# Borden-Arus.net
KiCad netlist of a schematic drawn in EAGLE
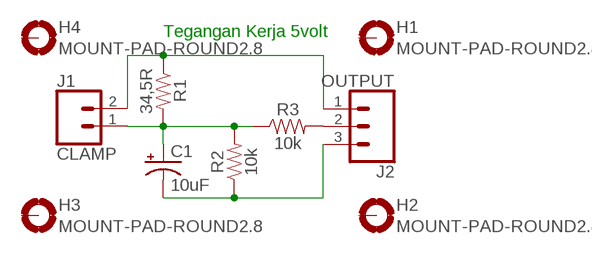
[diagram p0: schematic, sheet 1]

(export (version "E")
  (design (tool "Eeschema 10.0.6"))
  (components
    (comp (ref "C1")
      (value "10uF")
      (footprint "eagle-import:CPOL-RADIAL-2.5MM-5MM")
      (libsource (lib "eagle-import") (part "10UF-POLAR-RADIAL-2.5MM-25V-20%"))
    )
    (comp (ref "H1")
      (value "MOUNT-PAD-ROUND2.8")
      (footprint "eagle-import:2,8-PAD")
      (libsource (lib "eagle-import") (part "MOUNT-PAD-ROUND2.8"))
    )
    (comp (ref "H2")
      (value "MOUNT-PAD-ROUND2.8")
      (footprint "eagle-import:2,8-PAD")
      (libsource (lib "eagle-import") (part "MOUNT-PAD-ROUND2.8"))
    )
    (comp (ref "H3")
      (value "MOUNT-PAD-ROUND2.8")
      (footprint "eagle-import:2,8-PAD")
      (libsource (lib "eagle-import") (part "MOUNT-PAD-ROUND2.8"))
    )
    (comp (ref "H4")
      (value "MOUNT-PAD-ROUND2.8")
      (footprint "eagle-import:2,8-PAD")
      (libsource (lib "eagle-import") (part "MOUNT-PAD-ROUND2.8"))
    )
    (comp (ref "J1")
      (value "CLAMP")
      (footprint "eagle-import:1X02")
      (libsource (lib "eagle-import") (part "CONN_02"))
    )
    (comp (ref "J2")
      (value "OUTPUT")
      (footprint "eagle-import:1X03")
      (libsource (lib "eagle-import") (part "CONN_03"))
    )
    (comp (ref "R1")
      (value "34,5R")
      (footprint "eagle-import:AXIAL-0.3")
      (libsource (lib "eagle-import") (part "1KOHM-HORIZ-1/4W-1%"))
    )
    (comp (ref "R2")
      (value "10k")
      (footprint "eagle-import:AXIAL-0.3")
      (libsource (lib "eagle-import") (part "1KOHM-HORIZ-1/4W-1%"))
    )
    (comp (ref "R3")
      (value "10k")
      (footprint "eagle-import:AXIAL-0.3")
      (libsource (lib "eagle-import") (part "1KOHM-HORIZ-1/4W-1%"))
    )
  )
  (nets
    (net (code "1") (name "Net-(C1-+)") (class "Default")
      (node (ref "C1") (pin "1") (pinfunction "+_1") (pintype "passive"))
      (node (ref "J1") (pin "1") (pinfunction "1_1") (pintype "passive"))
      (node (ref "R1") (pin "P$2") (pinfunction "2_P$2") (pintype "passive"))
      (node (ref "R2") (pin "P$2") (pinfunction "2_P$2") (pintype "passive"))
      (node (ref "R3") (pin "P$1") (pinfunction "1_P$1") (pintype "passive"))
    )
    (net (code "2") (name "Net-(C1--)") (class "Default")
      (node (ref "C1") (pin "2") (pinfunction "-_2") (pintype "passive"))
      (node (ref "J2") (pin "3") (pinfunction "3_3") (pintype "passive"))
      (node (ref "R2") (pin "P$1") (pinfunction "1_P$1") (pintype "passive"))
    )
    (net (code "3") (name "Net-(R1-1)") (class "Default")
      (node (ref "J1") (pin "2") (pinfunction "2_2") (pintype "passive"))
      (node (ref "J2") (pin "1") (pinfunction "1_1") (pintype "passive"))
      (node (ref "R1") (pin "P$1") (pinfunction "1_P$1") (pintype "passive"))
    )
    (net (code "4") (name "Net-(R3-2)") (class "Default")
      (node (ref "J2") (pin "2") (pinfunction "2_2") (pintype "passive"))
      (node (ref "R3") (pin "P$2") (pinfunction "2_P$2") (pintype "passive"))
    )
    (net (code "5") (name "unconnected-(H1-MOUNT-PadB2,8)") (class "Default")
      (node (ref "H1") (pin "B2,8") (pinfunction "MOUNT_B2,8") (pintype "passive"))
    )
    (net (code "6") (name "unconnected-(H2-MOUNT-PadB2,8)") (class "Default")
      (node (ref "H2") (pin "B2,8") (pinfunction "MOUNT_B2,8") (pintype "passive"))
    )
    (net (code "7") (name "unconnected-(H3-MOUNT-PadB2,8)") (class "Default")
      (node (ref "H3") (pin "B2,8") (pinfunction "MOUNT_B2,8") (pintype "passive"))
    )
    (net (code "8") (name "unconnected-(H4-MOUNT-PadB2,8)") (class "Default")
      (node (ref "H4") (pin "B2,8") (pinfunction "MOUNT_B2,8") (pintype "passive"))
    )
  )
)
